# modulo_sensores.net
KiCad netlist of a schematic drawn in EAGLE
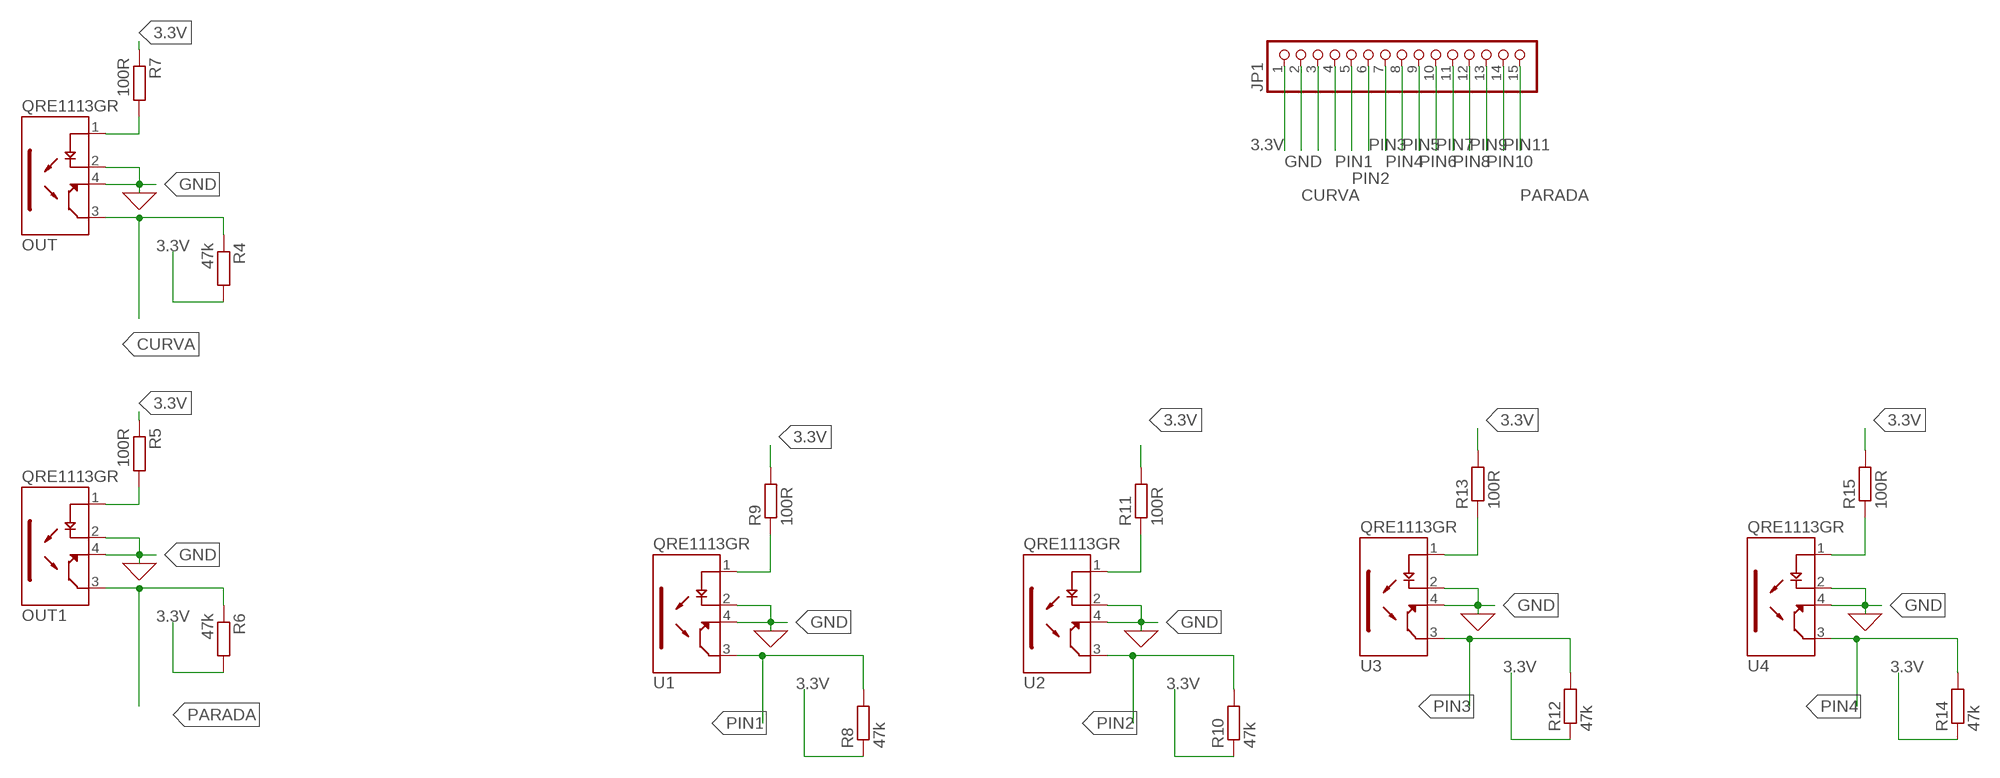
[diagram p0: schematic, sheet 1, part 1 of 2]
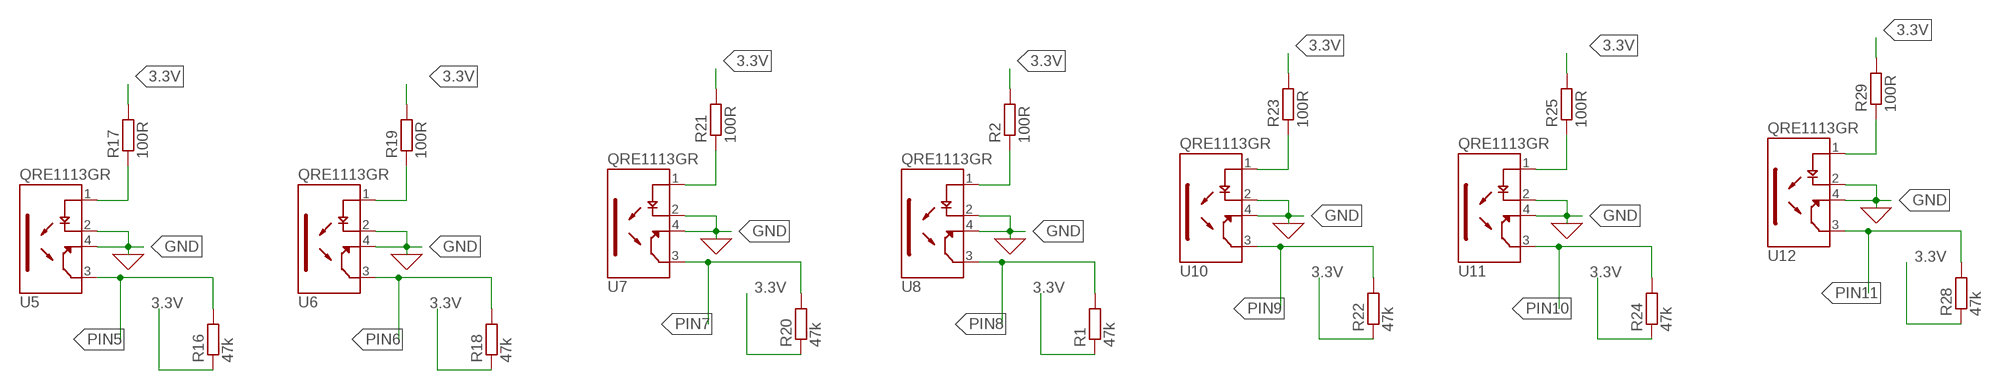
[diagram p1: schematic, sheet 1, part 2 of 2]

(export (version "E")
  (design (tool "Eeschema 10.0.6"))
  (components
    (comp (ref "JP1")
      (value "PINHD-1X15")
      (footprint "eagle-import:1X15")
      (libsource (lib "eagle-import") (part "PINHD-1X15"))
    )
    (comp (ref "OUT")
      (value "QRE1113GR")
      (footprint "eagle-import:SOIC180P460X187-4N")
      (fields (field (name "MF") "ON Semiconductor"))
      (libsource (lib "eagle-import") (part "QRE1113GR"))
    )
    (comp (ref "OUT1")
      (value "QRE1113GR")
      (footprint "eagle-import:SOIC180P460X187-4N")
      (fields (field (name "MF") "ON Semiconductor"))
      (libsource (lib "eagle-import") (part "QRE1113GR"))
    )
    (comp (ref "R1")
      (value "47k")
      (footprint "eagle-import:M0805")
      (libsource (lib "eagle-import") (part "R-EU_M0805"))
    )
    (comp (ref "R2")
      (value "100R")
      (footprint "eagle-import:M0805")
      (libsource (lib "eagle-import") (part "R-EU_M0805"))
    )
    (comp (ref "R4")
      (value "47k")
      (footprint "eagle-import:R0805")
      (libsource (lib "eagle-import") (part "R-EU_R0805"))
    )
    (comp (ref "R5")
      (value "100R")
      (footprint "eagle-import:R0805")
      (libsource (lib "eagle-import") (part "R-EU_R0805"))
    )
    (comp (ref "R6")
      (value "47k")
      (footprint "eagle-import:R0805")
      (libsource (lib "eagle-import") (part "R-EU_R0805"))
    )
    (comp (ref "R7")
      (value "100R")
      (footprint "eagle-import:R0805")
      (libsource (lib "eagle-import") (part "R-EU_R0805"))
    )
    (comp (ref "R8")
      (value "47k")
      (footprint "eagle-import:M0805")
      (libsource (lib "eagle-import") (part "R-EU_M0805"))
    )
    (comp (ref "R9")
      (value "100R")
      (footprint "eagle-import:M0805")
      (libsource (lib "eagle-import") (part "R-EU_M0805"))
    )
    (comp (ref "R10")
      (value "47k")
      (footprint "eagle-import:M0805")
      (libsource (lib "eagle-import") (part "R-EU_M0805"))
    )
    (comp (ref "R11")
      (value "100R")
      (footprint "eagle-import:M0805")
      (libsource (lib "eagle-import") (part "R-EU_M0805"))
    )
    (comp (ref "R12")
      (value "47k")
      (footprint "eagle-import:M0805")
      (libsource (lib "eagle-import") (part "R-EU_M0805"))
    )
    (comp (ref "R13")
      (value "100R")
      (footprint "eagle-import:M0805")
      (libsource (lib "eagle-import") (part "R-EU_M0805"))
    )
    (comp (ref "R14")
      (value "47k")
      (footprint "eagle-import:M0805")
      (libsource (lib "eagle-import") (part "R-EU_M0805"))
    )
    (comp (ref "R15")
      (value "100R")
      (footprint "eagle-import:M0805")
      (libsource (lib "eagle-import") (part "R-EU_M0805"))
    )
    (comp (ref "R16")
      (value "47k")
      (footprint "eagle-import:M0805")
      (libsource (lib "eagle-import") (part "R-EU_M0805"))
    )
    (comp (ref "R17")
      (value "100R")
      (footprint "eagle-import:M0805")
      (libsource (lib "eagle-import") (part "R-EU_M0805"))
    )
    (comp (ref "R18")
      (value "47k")
      (footprint "eagle-import:M0805")
      (libsource (lib "eagle-import") (part "R-EU_M0805"))
    )
    (comp (ref "R19")
      (value "100R")
      (footprint "eagle-import:M0805")
      (libsource (lib "eagle-import") (part "R-EU_M0805"))
    )
    (comp (ref "R20")
      (value "47k")
      (footprint "eagle-import:M0805")
      (libsource (lib "eagle-import") (part "R-EU_M0805"))
    )
    (comp (ref "R21")
      (value "100R")
      (footprint "eagle-import:M0805")
      (libsource (lib "eagle-import") (part "R-EU_M0805"))
    )
    (comp (ref "R22")
      (value "47k")
      (footprint "eagle-import:M0805")
      (libsource (lib "eagle-import") (part "R-EU_M0805"))
    )
    (comp (ref "R23")
      (value "100R")
      (footprint "eagle-import:M0805")
      (libsource (lib "eagle-import") (part "R-EU_M0805"))
    )
    (comp (ref "R24")
      (value "47k")
      (footprint "eagle-import:M0805")
      (libsource (lib "eagle-import") (part "R-EU_M0805"))
    )
    (comp (ref "R25")
      (value "100R")
      (footprint "eagle-import:M0805")
      (libsource (lib "eagle-import") (part "R-EU_M0805"))
    )
    (comp (ref "R28")
      (value "47k")
      (footprint "eagle-import:M0805")
      (libsource (lib "eagle-import") (part "R-EU_M0805"))
    )
    (comp (ref "R29")
      (value "100R")
      (footprint "eagle-import:M0805")
      (libsource (lib "eagle-import") (part "R-EU_M0805"))
    )
    (comp (ref "U1")
      (value "QRE1113GR")
      (footprint "eagle-import:SOIC180P460X187-4N")
      (fields (field (name "MF") "ON Semiconductor"))
      (libsource (lib "eagle-import") (part "QRE1113GR"))
    )
    (comp (ref "U2")
      (value "QRE1113GR")
      (footprint "eagle-import:SOIC180P460X187-4N")
      (fields (field (name "MF") "ON Semiconductor"))
      (libsource (lib "eagle-import") (part "QRE1113GR"))
    )
    (comp (ref "U3")
      (value "QRE1113GR")
      (footprint "eagle-import:SOIC180P460X187-4N")
      (fields (field (name "MF") "ON Semiconductor"))
      (libsource (lib "eagle-import") (part "QRE1113GR"))
    )
    (comp (ref "U4")
      (value "QRE1113GR")
      (footprint "eagle-import:SOIC180P460X187-4N")
      (fields (field (name "MF") "ON Semiconductor"))
      (libsource (lib "eagle-import") (part "QRE1113GR"))
    )
    (comp (ref "U5")
      (value "QRE1113GR")
      (footprint "eagle-import:SOIC180P460X187-4N")
      (fields (field (name "MF") "ON Semiconductor"))
      (libsource (lib "eagle-import") (part "QRE1113GR"))
    )
    (comp (ref "U6")
      (value "QRE1113GR")
      (footprint "eagle-import:SOIC180P460X187-4N")
      (fields (field (name "MF") "ON Semiconductor"))
      (libsource (lib "eagle-import") (part "QRE1113GR"))
    )
    (comp (ref "U7")
      (value "QRE1113GR")
      (footprint "eagle-import:SOIC180P460X187-4N")
      (fields (field (name "MF") "ON Semiconductor"))
      (libsource (lib "eagle-import") (part "QRE1113GR"))
    )
    (comp (ref "U8")
      (value "QRE1113GR")
      (footprint "eagle-import:SOIC180P460X187-4N")
      (fields (field (name "MF") "ON Semiconductor"))
      (libsource (lib "eagle-import") (part "QRE1113GR"))
    )
    (comp (ref "U10")
      (value "QRE1113GR")
      (footprint "eagle-import:SOIC180P460X187-4N")
      (fields (field (name "MF") "ON Semiconductor"))
      (libsource (lib "eagle-import") (part "QRE1113GR"))
    )
    (comp (ref "U11")
      (value "QRE1113GR")
      (footprint "eagle-import:SOIC180P460X187-4N")
      (fields (field (name "MF") "ON Semiconductor"))
      (libsource (lib "eagle-import") (part "QRE1113GR"))
    )
    (comp (ref "U12")
      (value "QRE1113GR")
      (footprint "eagle-import:SOIC180P460X187-4N")
      (fields (field (name "MF") "ON Semiconductor"))
      (libsource (lib "eagle-import") (part "QRE1113GR"))
    )
  )
  (nets
    (net (code "1") (name "3.3V") (class "Default")
      (node (ref "JP1") (pin "1") (pinfunction "1_1") (pintype "passive"))
      (node (ref "R1") (pin "1") (pinfunction "1_1") (pintype "passive"))
      (node (ref "R10") (pin "1") (pinfunction "1_1") (pintype "passive"))
      (node (ref "R11") (pin "2") (pinfunction "2_2") (pintype "passive"))
      (node (ref "R12") (pin "1") (pinfunction "1_1") (pintype "passive"))
      (node (ref "R13") (pin "2") (pinfunction "2_2") (pintype "passive"))
      (node (ref "R14") (pin "1") (pinfunction "1_1") (pintype "passive"))
      (node (ref "R15") (pin "2") (pinfunction "2_2") (pintype "passive"))
      (node (ref "R16") (pin "1") (pinfunction "1_1") (pintype "passive"))
      (node (ref "R17") (pin "2") (pinfunction "2_2") (pintype "passive"))
      (node (ref "R18") (pin "1") (pinfunction "1_1") (pintype "passive"))
      (node (ref "R19") (pin "2") (pinfunction "2_2") (pintype "passive"))
      (node (ref "R2") (pin "2") (pinfunction "2_2") (pintype "passive"))
      (node (ref "R20") (pin "1") (pinfunction "1_1") (pintype "passive"))
      (node (ref "R21") (pin "2") (pinfunction "2_2") (pintype "passive"))
      (node (ref "R22") (pin "1") (pinfunction "1_1") (pintype "passive"))
      (node (ref "R23") (pin "2") (pinfunction "2_2") (pintype "passive"))
      (node (ref "R24") (pin "1") (pinfunction "1_1") (pintype "passive"))
      (node (ref "R25") (pin "2") (pinfunction "2_2") (pintype "passive"))
      (node (ref "R28") (pin "1") (pinfunction "1_1") (pintype "passive"))
      (node (ref "R29") (pin "2") (pinfunction "2_2") (pintype "passive"))
      (node (ref "R4") (pin "2") (pinfunction "2_2") (pintype "passive"))
      (node (ref "R5") (pin "1") (pinfunction "1_1") (pintype "passive"))
      (node (ref "R6") (pin "2") (pinfunction "2_2") (pintype "passive"))
      (node (ref "R7") (pin "1") (pinfunction "1_1") (pintype "passive"))
      (node (ref "R8") (pin "1") (pinfunction "1_1") (pintype "passive"))
      (node (ref "R9") (pin "2") (pinfunction "2_2") (pintype "passive"))
    )
    (net (code "2") (name "CURVA") (class "Default")
      (node (ref "JP1") (pin "3") (pinfunction "3_3") (pintype "passive"))
      (node (ref "OUT") (pin "3") (pinfunction "CT_3") (pintype "passive"))
      (node (ref "R4") (pin "1") (pinfunction "1_1") (pintype "passive"))
    )
    (net (code "3") (name "GND") (class "Default")
      (node (ref "JP1") (pin "2") (pinfunction "2_2") (pintype "passive"))
      (node (ref "OUT") (pin "2") (pinfunction "C_2") (pintype "passive"))
      (node (ref "OUT") (pin "4") (pinfunction "ET_4") (pintype "passive"))
      (node (ref "OUT1") (pin "2") (pinfunction "C_2") (pintype "passive"))
      (node (ref "OUT1") (pin "4") (pinfunction "ET_4") (pintype "passive"))
      (node (ref "U1") (pin "2") (pinfunction "C_2") (pintype "passive"))
      (node (ref "U1") (pin "4") (pinfunction "ET_4") (pintype "passive"))
      (node (ref "U10") (pin "2") (pinfunction "C_2") (pintype "passive"))
      (node (ref "U10") (pin "4") (pinfunction "ET_4") (pintype "passive"))
      (node (ref "U11") (pin "2") (pinfunction "C_2") (pintype "passive"))
      (node (ref "U11") (pin "4") (pinfunction "ET_4") (pintype "passive"))
      (node (ref "U12") (pin "2") (pinfunction "C_2") (pintype "passive"))
      (node (ref "U12") (pin "4") (pinfunction "ET_4") (pintype "passive"))
      (node (ref "U2") (pin "2") (pinfunction "C_2") (pintype "passive"))
      (node (ref "U2") (pin "4") (pinfunction "ET_4") (pintype "passive"))
      (node (ref "U3") (pin "2") (pinfunction "C_2") (pintype "passive"))
      (node (ref "U3") (pin "4") (pinfunction "ET_4") (pintype "passive"))
      (node (ref "U4") (pin "2") (pinfunction "C_2") (pintype "passive"))
      (node (ref "U4") (pin "4") (pinfunction "ET_4") (pintype "passive"))
      (node (ref "U5") (pin "2") (pinfunction "C_2") (pintype "passive"))
      (node (ref "U5") (pin "4") (pinfunction "ET_4") (pintype "passive"))
      (node (ref "U6") (pin "2") (pinfunction "C_2") (pintype "passive"))
      (node (ref "U6") (pin "4") (pinfunction "ET_4") (pintype "passive"))
      (node (ref "U7") (pin "2") (pinfunction "C_2") (pintype "passive"))
      (node (ref "U7") (pin "4") (pinfunction "ET_4") (pintype "passive"))
      (node (ref "U8") (pin "2") (pinfunction "C_2") (pintype "passive"))
      (node (ref "U8") (pin "4") (pinfunction "ET_4") (pintype "passive"))
    )
    (net (code "4") (name "Net-(OUT-A)") (class "Default")
      (node (ref "OUT") (pin "1") (pinfunction "A_1") (pintype "passive"))
      (node (ref "R7") (pin "2") (pinfunction "2_2") (pintype "passive"))
    )
    (net (code "5") (name "Net-(OUT1-A)") (class "Default")
      (node (ref "OUT1") (pin "1") (pinfunction "A_1") (pintype "passive"))
      (node (ref "R5") (pin "2") (pinfunction "2_2") (pintype "passive"))
    )
    (net (code "6") (name "Net-(U1-A)") (class "Default")
      (node (ref "R9") (pin "1") (pinfunction "1_1") (pintype "passive"))
      (node (ref "U1") (pin "1") (pinfunction "A_1") (pintype "passive"))
    )
    (net (code "7") (name "Net-(U2-A)") (class "Default")
      (node (ref "R11") (pin "1") (pinfunction "1_1") (pintype "passive"))
      (node (ref "U2") (pin "1") (pinfunction "A_1") (pintype "passive"))
    )
    (net (code "8") (name "Net-(U3-A)") (class "Default")
      (node (ref "R13") (pin "1") (pinfunction "1_1") (pintype "passive"))
      (node (ref "U3") (pin "1") (pinfunction "A_1") (pintype "passive"))
    )
    (net (code "9") (name "Net-(U4-A)") (class "Default")
      (node (ref "R15") (pin "1") (pinfunction "1_1") (pintype "passive"))
      (node (ref "U4") (pin "1") (pinfunction "A_1") (pintype "passive"))
    )
    (net (code "10") (name "Net-(U5-A)") (class "Default")
      (node (ref "R17") (pin "1") (pinfunction "1_1") (pintype "passive"))
      (node (ref "U5") (pin "1") (pinfunction "A_1") (pintype "passive"))
    )
    (net (code "11") (name "Net-(U6-A)") (class "Default")
      (node (ref "R19") (pin "1") (pinfunction "1_1") (pintype "passive"))
      (node (ref "U6") (pin "1") (pinfunction "A_1") (pintype "passive"))
    )
    (net (code "12") (name "Net-(U7-A)") (class "Default")
      (node (ref "R21") (pin "1") (pinfunction "1_1") (pintype "passive"))
      (node (ref "U7") (pin "1") (pinfunction "A_1") (pintype "passive"))
    )
    (net (code "13") (name "Net-(U8-A)") (class "Default")
      (node (ref "R2") (pin "1") (pinfunction "1_1") (pintype "passive"))
      (node (ref "U8") (pin "1") (pinfunction "A_1") (pintype "passive"))
    )
    (net (code "14") (name "Net-(U10-A)") (class "Default")
      (node (ref "R23") (pin "1") (pinfunction "1_1") (pintype "passive"))
      (node (ref "U10") (pin "1") (pinfunction "A_1") (pintype "passive"))
    )
    (net (code "15") (name "Net-(U11-A)") (class "Default")
      (node (ref "R25") (pin "1") (pinfunction "1_1") (pintype "passive"))
      (node (ref "U11") (pin "1") (pinfunction "A_1") (pintype "passive"))
    )
    (net (code "16") (name "Net-(U12-A)") (class "Default")
      (node (ref "R29") (pin "1") (pinfunction "1_1") (pintype "passive"))
      (node (ref "U12") (pin "1") (pinfunction "A_1") (pintype "passive"))
    )
    (net (code "17") (name "PARADA") (class "Default")
      (node (ref "JP1") (pin "15") (pinfunction "15_15") (pintype "passive"))
      (node (ref "OUT1") (pin "3") (pinfunction "CT_3") (pintype "passive"))
      (node (ref "R6") (pin "1") (pinfunction "1_1") (pintype "passive"))
    )
    (net (code "18") (name "PIN1") (class "Default")
      (node (ref "JP1") (pin "4") (pinfunction "4_4") (pintype "passive"))
      (node (ref "R8") (pin "2") (pinfunction "2_2") (pintype "passive"))
      (node (ref "U1") (pin "3") (pinfunction "CT_3") (pintype "passive"))
    )
    (net (code "19") (name "PIN2") (class "Default")
      (node (ref "JP1") (pin "5") (pinfunction "5_5") (pintype "passive"))
      (node (ref "R10") (pin "2") (pinfunction "2_2") (pintype "passive"))
      (node (ref "U2") (pin "3") (pinfunction "CT_3") (pintype "passive"))
    )
    (net (code "20") (name "PIN3") (class "Default")
      (node (ref "JP1") (pin "6") (pinfunction "6_6") (pintype "passive"))
      (node (ref "R12") (pin "2") (pinfunction "2_2") (pintype "passive"))
      (node (ref "U3") (pin "3") (pinfunction "CT_3") (pintype "passive"))
    )
    (net (code "21") (name "PIN4") (class "Default")
      (node (ref "JP1") (pin "7") (pinfunction "7_7") (pintype "passive"))
      (node (ref "R14") (pin "2") (pinfunction "2_2") (pintype "passive"))
      (node (ref "U4") (pin "3") (pinfunction "CT_3") (pintype "passive"))
    )
    (net (code "22") (name "PIN5") (class "Default")
      (node (ref "JP1") (pin "8") (pinfunction "8_8") (pintype "passive"))
      (node (ref "R16") (pin "2") (pinfunction "2_2") (pintype "passive"))
      (node (ref "U5") (pin "3") (pinfunction "CT_3") (pintype "passive"))
    )
    (net (code "23") (name "PIN6") (class "Default")
      (node (ref "JP1") (pin "9") (pinfunction "9_9") (pintype "passive"))
      (node (ref "R18") (pin "2") (pinfunction "2_2") (pintype "passive"))
      (node (ref "U6") (pin "3") (pinfunction "CT_3") (pintype "passive"))
    )
    (net (code "24") (name "PIN7") (class "Default")
      (node (ref "JP1") (pin "10") (pinfunction "10_10") (pintype "passive"))
      (node (ref "R20") (pin "2") (pinfunction "2_2") (pintype "passive"))
      (node (ref "U7") (pin "3") (pinfunction "CT_3") (pintype "passive"))
    )
    (net (code "25") (name "PIN8") (class "Default")
      (node (ref "JP1") (pin "11") (pinfunction "11_11") (pintype "passive"))
      (node (ref "R1") (pin "2") (pinfunction "2_2") (pintype "passive"))
      (node (ref "U8") (pin "3") (pinfunction "CT_3") (pintype "passive"))
    )
    (net (code "26") (name "PIN9") (class "Default")
      (node (ref "JP1") (pin "12") (pinfunction "12_12") (pintype "passive"))
      (node (ref "R22") (pin "2") (pinfunction "2_2") (pintype "passive"))
      (node (ref "U10") (pin "3") (pinfunction "CT_3") (pintype "passive"))
    )
    (net (code "27") (name "PIN10") (class "Default")
      (node (ref "JP1") (pin "13") (pinfunction "13_13") (pintype "passive"))
      (node (ref "R24") (pin "2") (pinfunction "2_2") (pintype "passive"))
      (node (ref "U11") (pin "3") (pinfunction "CT_3") (pintype "passive"))
    )
    (net (code "28") (name "PIN11") (class "Default")
      (node (ref "JP1") (pin "14") (pinfunction "14_14") (pintype "passive"))
      (node (ref "R28") (pin "2") (pinfunction "2_2") (pintype "passive"))
      (node (ref "U12") (pin "3") (pinfunction "CT_3") (pintype "passive"))
    )
  )
)
